# Sheet2.net
KiCad netlist of a schematic drawn in Altium Designer
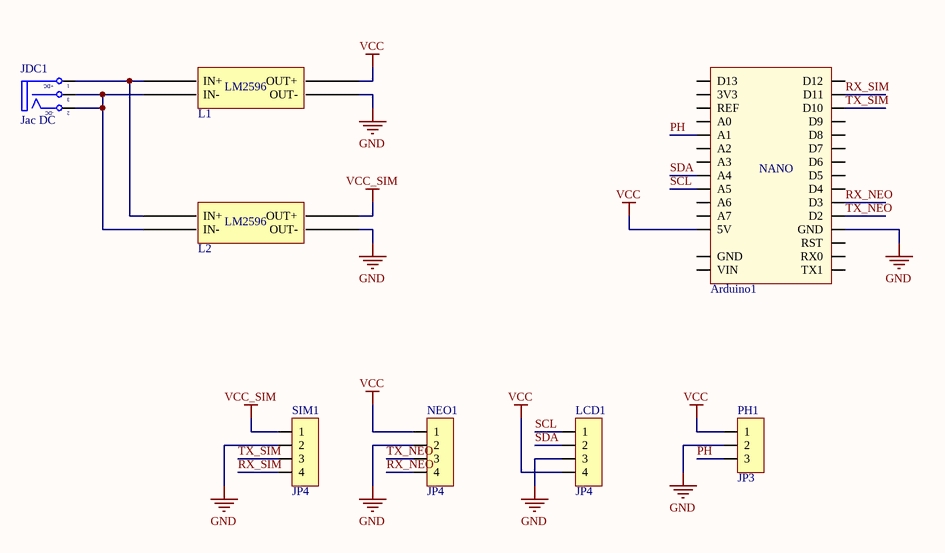
[diagram p0: Sheet2.SchDoc]

(export (version "E")
  (design (tool "Eeschema 10.0.6"))
  (components
    (comp (ref "Arduino1")
      (value "Arduino Nano")
      (footprint "Arduino Nano")
      (description "Arduino NANO")
      (libsource (lib "LIBRARY") (part "Arduino Nano"))
    )
    (comp (ref "JDC1")
      (value "Jac DC")
      (footprint "DC0")
      (description "Jac DC input")
      (libsource (lib "LIBRARY") (part "DCIN"))
    )
    (comp (ref "L1")
      (value "BUCK_LM2596")
      (footprint "BUCK_LM2596")
      (libsource (lib "BUCK_LM2596_Sch") (part "BUCK_LM2596"))
    )
    (comp (ref "L2")
      (value "BUCK_LM2596")
      (footprint "BUCK_LM2596")
      (libsource (lib "BUCK_LM2596_Sch") (part "BUCK_LM2596"))
    )
    (comp (ref "LCD1")
      (value "JP4")
      (footprint "JP4-C1T")
      (description "WR-PHD 2.54 mm Angled Socket Header")
      (fields
        (field (name "MANUFACTURER") "Würth Elektronik eiSos GmbH")
        (field (name "PARTNO") "613004143121")
        (field (name "CREATED BY") "Karrer Zheng")
      )
      (libsource (lib "LIBRARY") (part "JP4"))
    )
    (comp (ref "NEO1")
      (value "JP4")
      (footprint "JP4-C1T")
      (description "WR-PHD 2.54 mm Angled Socket Header")
      (fields
        (field (name "MANUFACTURER") "Würth Elektronik eiSos GmbH")
        (field (name "PARTNO") "613004143121")
        (field (name "CREATED BY") "Karrer Zheng")
      )
      (libsource (lib "LIBRARY") (part "JP4"))
    )
    (comp (ref "PH1")
      (value "JP3")
      (footprint "JP3-C1T")
      (description "WR-PHD 2.54 mm Angled Socket Header")
      (fields
        (field (name "MANUFACTURER") "Würth Elektronik eiSos GmbH")
        (field (name "PARTNO") "613003143121")
        (field (name "CREATED BY") "Karrer Zheng")
      )
      (libsource (lib "LIBRARY") (part "JP3"))
    )
    (comp (ref "SIM1")
      (value "JP4")
      (footprint "JP4-C1T")
      (description "WR-PHD 2.54 mm Angled Socket Header")
      (fields
        (field (name "MANUFACTURER") "Würth Elektronik eiSos GmbH")
        (field (name "PARTNO") "613004143121")
        (field (name "CREATED BY") "Karrer Zheng")
      )
      (libsource (lib "LIBRARY") (part "JP4"))
    )
  )
  (nets
    (net (code "1") (name "/PH") (class "Default")
      (node (ref "Arduino1") (pin "A1") (pinfunction "A1_A1") (pintype "passive"))
      (node (ref "PH1") (pin "3") (pinfunction "3_3") (pintype "passive"))
    )
    (net (code "2") (name "/RX_NEO") (class "Default")
      (node (ref "Arduino1") (pin "D3") (pinfunction "D3_D3") (pintype "passive"))
      (node (ref "NEO1") (pin "4") (pinfunction "4_4") (pintype "passive"))
    )
    (net (code "3") (name "/RX_SIM") (class "Default")
      (node (ref "Arduino1") (pin "D11") (pinfunction "D11_D11") (pintype "passive"))
      (node (ref "SIM1") (pin "4") (pinfunction "4_4") (pintype "passive"))
    )
    (net (code "4") (name "/SCL") (class "Default")
      (node (ref "Arduino1") (pin "A5") (pinfunction "A5_A5") (pintype "passive"))
      (node (ref "LCD1") (pin "1") (pinfunction "1_1") (pintype "passive"))
    )
    (net (code "5") (name "/SDA") (class "Default")
      (node (ref "Arduino1") (pin "A4") (pinfunction "A4_A4") (pintype "passive"))
      (node (ref "LCD1") (pin "2") (pinfunction "2_2") (pintype "passive"))
    )
    (net (code "6") (name "/TX_NEO") (class "Default")
      (node (ref "Arduino1") (pin "D2") (pinfunction "D2_D2") (pintype "passive"))
      (node (ref "NEO1") (pin "3") (pinfunction "3_3") (pintype "passive"))
    )
    (net (code "7") (name "/TX_SIM") (class "Default")
      (node (ref "Arduino1") (pin "D10") (pinfunction "D10_D10") (pintype "passive"))
      (node (ref "SIM1") (pin "3") (pinfunction "3_3") (pintype "passive"))
    )
    (net (code "8") (name "GND") (class "Default")
      (node (ref "Arduino1") (pin "GND") (pinfunction "GND_GND") (pintype "passive"))
      (node (ref "L1") (pin "3") (pinfunction "OUT-_3") (pintype "passive"))
      (node (ref "L2") (pin "3") (pinfunction "OUT-_3") (pintype "passive"))
      (node (ref "LCD1") (pin "3") (pinfunction "3_3") (pintype "passive"))
      (node (ref "NEO1") (pin "2") (pinfunction "2_2") (pintype "passive"))
      (node (ref "PH1") (pin "2") (pinfunction "2_2") (pintype "passive"))
      (node (ref "SIM1") (pin "2") (pinfunction "2_2") (pintype "passive"))
    )
    (net (code "9") (name "Net-(JDC1-S)") (class "Default")
      (node (ref "JDC1") (pin "2") (pinfunction "TN_2") (pintype "passive"))
      (node (ref "JDC1") (pin "3") (pinfunction "S_3") (pintype "power_in"))
      (node (ref "L1") (pin "2") (pinfunction "IN-_2") (pintype "passive"))
      (node (ref "L2") (pin "2") (pinfunction "IN-_2") (pintype "passive"))
    )
    (net (code "10") (name "Net-(JDC1-T)") (class "Default")
      (node (ref "JDC1") (pin "1") (pinfunction "T_1") (pintype "passive"))
      (node (ref "L1") (pin "1") (pinfunction "IN+_1") (pintype "passive"))
      (node (ref "L2") (pin "1") (pinfunction "IN+_1") (pintype "passive"))
    )
    (net (code "11") (name "VCC") (class "Default")
      (node (ref "Arduino1") (pin "5V") (pinfunction "5V_5V") (pintype "passive"))
      (node (ref "L1") (pin "4") (pinfunction "OUT+_4") (pintype "passive"))
      (node (ref "LCD1") (pin "4") (pinfunction "4_4") (pintype "passive"))
      (node (ref "NEO1") (pin "1") (pinfunction "1_1") (pintype "passive"))
      (node (ref "PH1") (pin "1") (pinfunction "1_1") (pintype "passive"))
    )
    (net (code "12") (name "VCC_SIM") (class "Default")
      (node (ref "L2") (pin "4") (pinfunction "OUT+_4") (pintype "passive"))
      (node (ref "SIM1") (pin "1") (pinfunction "1_1") (pintype "passive"))
    )
    (net (code "13") (name "unconnected-(Arduino1-Pad3V3)") (class "Default")
      (node (ref "Arduino1") (pin "3V3") (pinfunction "3V3_3V3") (pintype "passive"))
    )
    (net (code "14") (name "unconnected-(Arduino1-PadA0)") (class "Default")
      (node (ref "Arduino1") (pin "A0") (pinfunction "A0_A0") (pintype "passive"))
    )
    (net (code "15") (name "unconnected-(Arduino1-PadA2)") (class "Default")
      (node (ref "Arduino1") (pin "A2") (pinfunction "A2_A2") (pintype "passive"))
    )
    (net (code "16") (name "unconnected-(Arduino1-PadA3)") (class "Default")
      (node (ref "Arduino1") (pin "A3") (pinfunction "A3_A3") (pintype "passive"))
    )
    (net (code "17") (name "unconnected-(Arduino1-PadA6)") (class "Default")
      (node (ref "Arduino1") (pin "A6") (pinfunction "A6_A6") (pintype "passive"))
    )
    (net (code "18") (name "unconnected-(Arduino1-PadA7)") (class "Default")
      (node (ref "Arduino1") (pin "A7") (pinfunction "A7_A7") (pintype "passive"))
    )
    (net (code "19") (name "unconnected-(Arduino1-PadD4)") (class "Default")
      (node (ref "Arduino1") (pin "D4") (pinfunction "D4_D4") (pintype "passive"))
    )
    (net (code "20") (name "unconnected-(Arduino1-PadD5)") (class "Default")
      (node (ref "Arduino1") (pin "D5") (pinfunction "D5_D5") (pintype "passive"))
    )
    (net (code "21") (name "unconnected-(Arduino1-PadD6)") (class "Default")
      (node (ref "Arduino1") (pin "D6") (pinfunction "D6_D6") (pintype "passive"))
    )
    (net (code "22") (name "unconnected-(Arduino1-PadD7)") (class "Default")
      (node (ref "Arduino1") (pin "D7") (pinfunction "D7_D7") (pintype "passive"))
    )
    (net (code "23") (name "unconnected-(Arduino1-PadD8)") (class "Default")
      (node (ref "Arduino1") (pin "D8") (pinfunction "D8_D8") (pintype "passive"))
    )
    (net (code "24") (name "unconnected-(Arduino1-PadD9)") (class "Default")
      (node (ref "Arduino1") (pin "D9") (pinfunction "D9_D9") (pintype "passive"))
    )
    (net (code "25") (name "unconnected-(Arduino1-PadD12)") (class "Default")
      (node (ref "Arduino1") (pin "D12") (pinfunction "D12_D12") (pintype "passive"))
    )
    (net (code "26") (name "unconnected-(Arduino1-PadD13)") (class "Default")
      (node (ref "Arduino1") (pin "D13") (pinfunction "D13_D13") (pintype "passive"))
    )
    (net (code "27") (name "unconnected-(Arduino1-PadGND)") (class "Default")
      (node (ref "Arduino1") (pin "GND") (pinfunction "GND_GND") (pintype "passive"))
    )
    (net (code "28") (name "unconnected-(Arduino1-PadREF)") (class "Default")
      (node (ref "Arduino1") (pin "REF") (pinfunction "REF_REF") (pintype "passive"))
    )
    (net (code "29") (name "unconnected-(Arduino1-PadRST)") (class "Default")
      (node (ref "Arduino1") (pin "RST") (pinfunction "RST_RST") (pintype "passive"))
    )
    (net (code "30") (name "unconnected-(Arduino1-PadRST)_1") (class "Default")
      (node (ref "Arduino1") (pin "RST") (pinfunction "RST_RST") (pintype "passive"))
    )
    (net (code "31") (name "unconnected-(Arduino1-PadRX0)") (class "Default")
      (node (ref "Arduino1") (pin "RX0") (pinfunction "RX0_RX0") (pintype "passive"))
    )
    (net (code "32") (name "unconnected-(Arduino1-PadTX1)") (class "Default")
      (node (ref "Arduino1") (pin "TX1") (pinfunction "TX1_TX1") (pintype "passive"))
    )
    (net (code "33") (name "unconnected-(Arduino1-PadVIN)") (class "Default")
      (node (ref "Arduino1") (pin "VIN") (pinfunction "VIN_VIN") (pintype "passive"))
    )
  )
)
